# AMP.net
KiCad netlist of a schematic drawn in Altium Designer
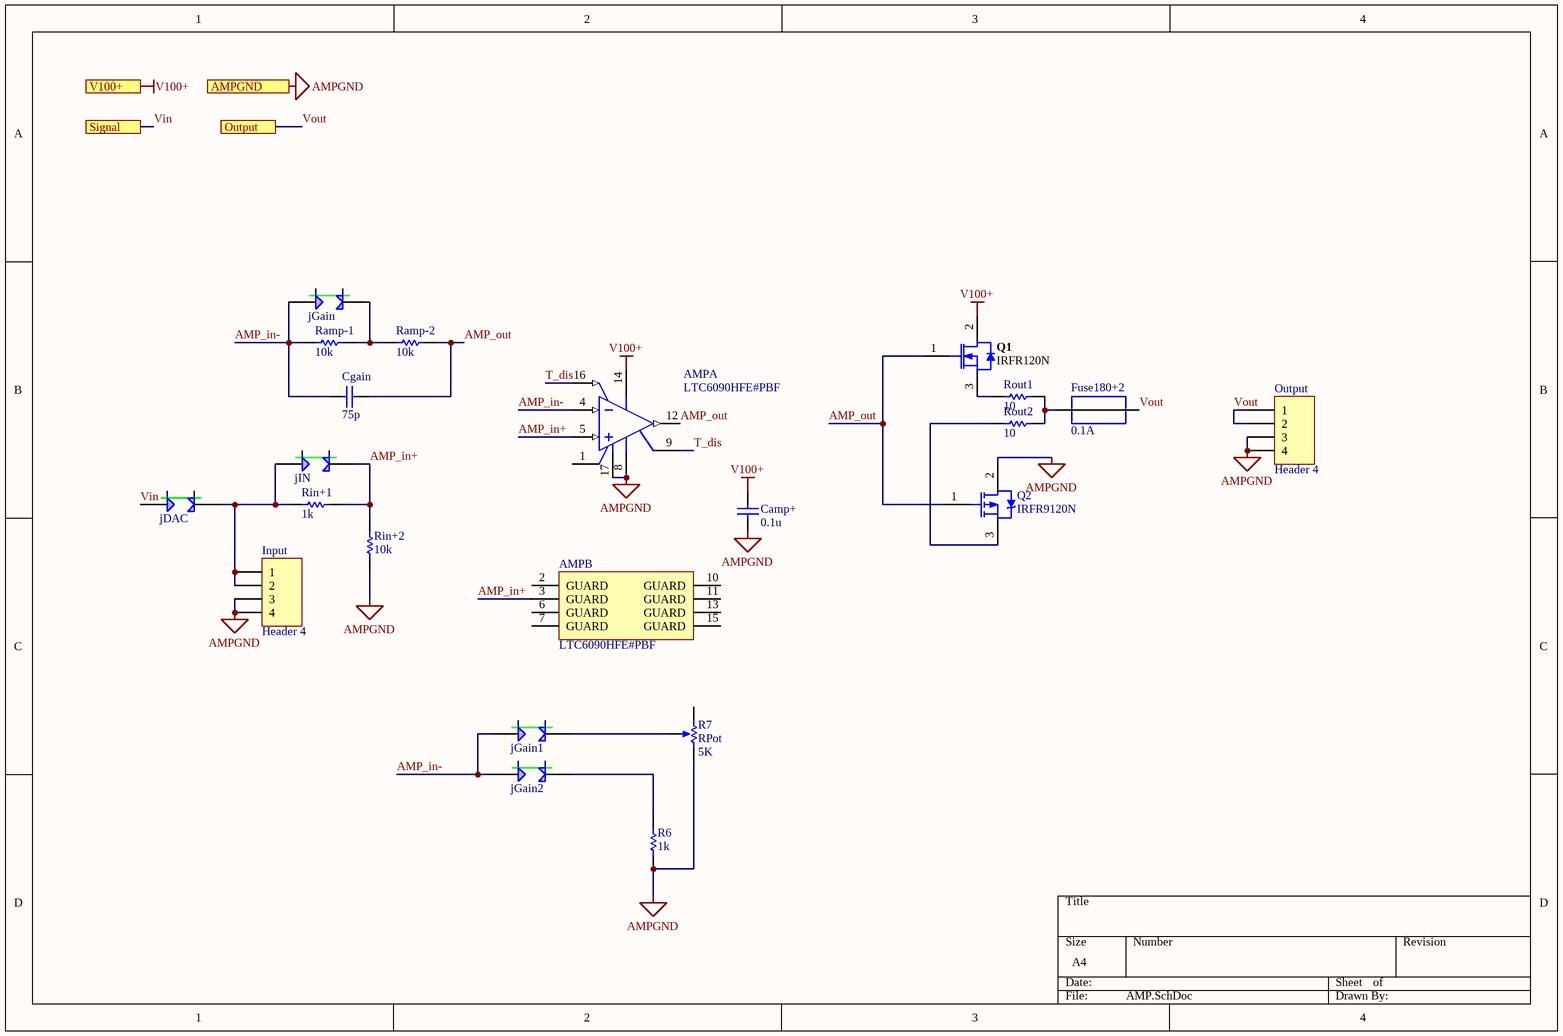
[diagram p0: AMP.SchDoc]

(export (version "E")
  (design (tool "Eeschema 10.0.6"))
  (components
    (comp (ref "AMP")
      (value "LTC6090HFE#PBF")
      (footprint "LT-FE-16-EPV-BA_N")
      (fields
        (field (name "LINEAR TECHNOLOGY PART NUMBER") "LTC6090")
        (field (name "MANUFACTURER") "Linear Technology")
      )
      (libsource (lib "Linear Technology Operational Amplifiers (LT2000-LT6000)") (part "LTC6090HFE#PBF"))
    )
    (comp (ref "Camp+")
      (value "0.1u")
      (footprint "C_0805")
      (description "Capacitor (Semiconductor SIM Model)")
      (fields (field (name "PARTNO") "445-6808-1-ND"))
      (libsource (lib "Lib_AMNL") (part "Csemi"))
    )
    (comp (ref "Cgain")
      (value "75p")
      (footprint "AXIAL-0.5")
      (description "Capacitor (Semiconductor SIM Model)")
      (fields (field (name "PARTNO") "?"))
      (libsource (lib "Lib_AMNL") (part "Cfilm"))
    )
    (comp (ref "Fuse180+2")
      (value "0.1A")
      (footprint "FuseHolder")
      (fields (field (name "PARTNO") "?") (field (name "Comment") "Fuse"))
      (libsource (lib "Lib_AMNL") (part "Fuse"))
    )
    (comp (ref "Input")
      (value "Header 4")
      (footprint "HDR1X4")
      (description "Header, 4-Pin")
      (fields (field (name "PUBLISHER") "Altium Limited"))
      (libsource (lib "Miscellaneous Connectors") (part "Header 4"))
    )
    (comp (ref "jDAC")
      (value "Jumper")
      (footprint "HDR1X2")
      (description "solderable jumper")
      (libsource (lib "Lib_AMNL") (part "Jumper"))
    )
    (comp (ref "jGain")
      (value "Jumper")
      (footprint "HDR1X2")
      (description "solderable jumper")
      (libsource (lib "Lib_AMNL") (part "Jumper"))
    )
    (comp (ref "jGain1")
      (value "Jumper")
      (footprint "HDR1X2")
      (description "solderable jumper")
      (libsource (lib "Lib_AMNL") (part "Jumper"))
    )
    (comp (ref "jGain2")
      (value "Jumper")
      (footprint "HDR1X2")
      (description "solderable jumper")
      (libsource (lib "Lib_AMNL") (part "Jumper"))
    )
    (comp (ref "jIN")
      (value "Jumper")
      (footprint "HDR1X2")
      (description "solderable jumper")
      (libsource (lib "Lib_AMNL") (part "Jumper"))
    )
    (comp (ref "Output")
      (value "Header 4")
      (footprint "HDR1X4")
      (description "Header, 4-Pin")
      (fields (field (name "PUBLISHER") "Altium Limited"))
      (libsource (lib "Miscellaneous Connectors") (part "Header 4"))
    )
    (comp (ref "Q1")
      (value "IRFR120N")
      (footprint "INF-PG-TO252")
      (fields (field (name "MANUFACTURER") "Infineon") (field (name "PARTNUMBER") "2N7002"))
      (libsource (lib "Infineon_Power_MOSFET") (part "IRFR120N"))
    )
    (comp (ref "Q2")
      (value "IRFR9120N")
      (footprint "INF-PG-TO252")
      (fields (field (name "MANUFACTURER") "Infineon") (field (name "PARTNUMBER") "BSL307SP"))
      (libsource (lib "Infineon_Power_MOSFET") (part "IRFR9120N"))
    )
    (comp (ref "R6")
      (value "1k")
      (footprint "0805")
      (description "Semiconductor Resistor, SMD")
      (fields (field (name "PARTNO") "?"))
      (libsource (lib "Lib_AMNL") (part "Rsemi"))
    )
    (comp (ref "R7")
      (value "RPot")
      (footprint "VR5")
      (description "Potentiometer")
      (fields (field (name "ALTIUM_VALUE") "5K") (field (name "PUBLISHER") "Altium Limited"))
      (libsource (lib "Miscellaneous Devices") (part "RPot"))
    )
    (comp (ref "Ramp-1")
      (value "10k")
      (footprint "AXIAL-0.5")
      (description "Semiconductor Resistor, SMD")
      (fields (field (name "PARTNO") "?"))
      (libsource (lib "Lib_AMNL") (part "Rth"))
    )
    (comp (ref "Ramp-2")
      (value "10k")
      (footprint "AXIAL-0.5")
      (description "Semiconductor Resistor, SMD")
      (fields (field (name "PARTNO") "?"))
      (libsource (lib "Lib_AMNL") (part "Rth"))
    )
    (comp (ref "Rin+1")
      (value "1k")
      (footprint "0805")
      (description "Semiconductor Resistor, SMD")
      (fields (field (name "PARTNO") "?"))
      (libsource (lib "Lib_AMNL") (part "Rsemi"))
    )
    (comp (ref "Rin+2")
      (value "10k")
      (footprint "0805")
      (description "Semiconductor Resistor, SMD")
      (fields (field (name "PARTNO") "?"))
      (libsource (lib "Lib_AMNL") (part "Rsemi"))
    )
    (comp (ref "Rout1")
      (value "10")
      (footprint "Res_5w")
      (description "Semiconductor Resistor, SMD")
      (fields (field (name "PARTNO") "?"))
      (libsource (lib "Lib_AMNL") (part "Rsemi"))
    )
    (comp (ref "Rout2")
      (value "10")
      (footprint "Res_5w")
      (description "Semiconductor Resistor, SMD")
      (fields (field (name "PARTNO") "?"))
      (libsource (lib "Lib_AMNL") (part "Rsemi"))
    )
  )
  (nets
    (net (code "1") (name "/AMP_in+") (class "Default")
      (node (ref "AMP") (pin "3") (pinfunction "GUARD_3") (pintype "passive"))
      (node (ref "AMP") (pin "5") (pinfunction "+IN_5") (pintype "input"))
      (node (ref "Rin+1") (pin "2") (pinfunction "2_2") (pintype "passive"))
      (node (ref "Rin+2") (pin "2") (pinfunction "2_2") (pintype "passive"))
      (node (ref "jIN") (pin "2") (pinfunction "2_2") (pintype "passive"))
    )
    (net (code "2") (name "/AMP_in-") (class "Default")
      (node (ref "AMP") (pin "4") (pinfunction "-IN_4") (pintype "input"))
      (node (ref "Cgain") (pin "1") (pinfunction "1_1") (pintype "passive"))
      (node (ref "Ramp-1") (pin "1") (pinfunction "1_1") (pintype "passive"))
      (node (ref "jGain") (pin "1") (pinfunction "1_1") (pintype "passive"))
      (node (ref "jGain1") (pin "1") (pinfunction "1_1") (pintype "passive"))
      (node (ref "jGain2") (pin "1") (pinfunction "1_1") (pintype "passive"))
    )
    (net (code "3") (name "/AMP_out") (class "Default")
      (node (ref "AMP") (pin "12") (pinfunction "OUT_12") (pintype "output"))
      (node (ref "Cgain") (pin "2") (pinfunction "2_2") (pintype "passive"))
      (node (ref "Q1") (pin "1") (pinfunction "GATE_1") (pintype "passive"))
      (node (ref "Q2") (pin "1") (pinfunction "GATE_1") (pintype "passive"))
      (node (ref "Ramp-2") (pin "2") (pinfunction "2_2") (pintype "passive"))
    )
    (net (code "4") (name "/T_dis") (class "Default")
      (node (ref "AMP") (pin "16") (pinfunction "~{OD}_16") (pintype "input"))
      (node (ref "AMP") (pin "9") (pinfunction "~{TFLAG}_9") (pintype "open_collector"))
    )
    (net (code "5") (name "/Vin") (class "Default")
      (node (ref "jDAC") (pin "1") (pinfunction "1_1") (pintype "passive"))
    )
    (net (code "6") (name "/Vout") (class "Default")
      (node (ref "Fuse180+2") (pin "2") (pinfunction "2_2") (pintype "power_in"))
      (node (ref "Output") (pin "1") (pinfunction "1_1") (pintype "passive"))
      (node (ref "Output") (pin "2") (pinfunction "2_2") (pintype "passive"))
    )
    (net (code "7") (name "AMPGND") (class "Default")
      (node (ref "AMP") (pin "17") (pinfunction "EP_17") (pintype "power_in"))
      (node (ref "AMP") (pin "8") (pinfunction "V-_8") (pintype "power_in"))
      (node (ref "Camp+") (pin "1") (pinfunction "1_1") (pintype "passive"))
      (node (ref "Input") (pin "3") (pinfunction "3_3") (pintype "passive"))
      (node (ref "Input") (pin "4") (pinfunction "4_4") (pintype "passive"))
      (node (ref "Output") (pin "3") (pinfunction "3_3") (pintype "passive"))
      (node (ref "Output") (pin "4") (pinfunction "4_4") (pintype "passive"))
      (node (ref "Q2") (pin "2") (pinfunction "DRAIN_2") (pintype "passive"))
      (node (ref "R6") (pin "1") (pinfunction "1_1") (pintype "passive"))
      (node (ref "R7") (pin "2") (pinfunction "BOT_2") (pintype "passive"))
      (node (ref "Rin+2") (pin "1") (pinfunction "1_1") (pintype "passive"))
    )
    (net (code "8") (name "Net-(Fuse180+2-Pad1)") (class "Default")
      (node (ref "Fuse180+2") (pin "1") (pinfunction "1_1") (pintype "power_in"))
      (node (ref "Rout1") (pin "2") (pinfunction "2_2") (pintype "passive"))
      (node (ref "Rout2") (pin "2") (pinfunction "2_2") (pintype "passive"))
    )
    (net (code "9") (name "Net-(Input-Pad1)") (class "Default")
      (node (ref "Input") (pin "1") (pinfunction "1_1") (pintype "passive"))
      (node (ref "Input") (pin "2") (pinfunction "2_2") (pintype "passive"))
      (node (ref "Rin+1") (pin "1") (pinfunction "1_1") (pintype "passive"))
      (node (ref "jDAC") (pin "2") (pinfunction "2_2") (pintype "passive"))
      (node (ref "jIN") (pin "1") (pinfunction "1_1") (pintype "passive"))
    )
    (net (code "10") (name "Net-(Q1-SOURCE)") (class "Default")
      (node (ref "Q1") (pin "3") (pinfunction "SOURCE_3") (pintype "passive"))
      (node (ref "Rout1") (pin "1") (pinfunction "1_1") (pintype "passive"))
    )
    (net (code "11") (name "Net-(Q2-SOURCE)") (class "Default")
      (node (ref "Q2") (pin "3") (pinfunction "SOURCE_3") (pintype "passive"))
      (node (ref "Rout2") (pin "1") (pinfunction "1_1") (pintype "passive"))
    )
    (net (code "12") (name "Net-(R6-Pad2)") (class "Default")
      (node (ref "R6") (pin "2") (pinfunction "2_2") (pintype "passive"))
      (node (ref "jGain2") (pin "2") (pinfunction "2_2") (pintype "passive"))
    )
    (net (code "13") (name "Net-(R7-TAP)") (class "Default")
      (node (ref "R7") (pin "3") (pinfunction "TAP_3") (pintype "passive"))
      (node (ref "jGain1") (pin "2") (pinfunction "2_2") (pintype "passive"))
    )
    (net (code "14") (name "Net-(Ramp-1-Pad2)") (class "Default")
      (node (ref "Ramp-1") (pin "2") (pinfunction "2_2") (pintype "passive"))
      (node (ref "Ramp-2") (pin "1") (pinfunction "1_1") (pintype "passive"))
      (node (ref "jGain") (pin "2") (pinfunction "2_2") (pintype "passive"))
    )
    (net (code "15") (name "V100+") (class "Default")
      (node (ref "AMP") (pin "14") (pinfunction "V+_14") (pintype "power_in"))
      (node (ref "Camp+") (pin "2") (pinfunction "2_2") (pintype "passive"))
      (node (ref "Q1") (pin "2") (pinfunction "DRAIN_2") (pintype "passive"))
    )
    (net (code "16") (name "unconnected-(AMPA-COM-Pad1)") (class "Default")
      (node (ref "AMP") (pin "1") (pinfunction "COM_1") (pintype "passive"))
    )
    (net (code "17") (name "unconnected-(AMPB-GUARD-Pad2)") (class "Default")
      (node (ref "AMP") (pin "2") (pinfunction "GUARD_2") (pintype "passive"))
    )
    (net (code "18") (name "unconnected-(AMPB-GUARD-Pad6)") (class "Default")
      (node (ref "AMP") (pin "6") (pinfunction "GUARD_6") (pintype "passive"))
    )
    (net (code "19") (name "unconnected-(AMPB-GUARD-Pad7)") (class "Default")
      (node (ref "AMP") (pin "7") (pinfunction "GUARD_7") (pintype "passive"))
    )
    (net (code "20") (name "unconnected-(AMPB-GUARD-Pad10)") (class "Default")
      (node (ref "AMP") (pin "10") (pinfunction "GUARD_10") (pintype "passive"))
    )
    (net (code "21") (name "unconnected-(AMPB-GUARD-Pad11)") (class "Default")
      (node (ref "AMP") (pin "11") (pinfunction "GUARD_11") (pintype "passive"))
    )
    (net (code "22") (name "unconnected-(AMPB-GUARD-Pad13)") (class "Default")
      (node (ref "AMP") (pin "13") (pinfunction "GUARD_13") (pintype "passive"))
    )
    (net (code "23") (name "unconnected-(AMPB-GUARD-Pad15)") (class "Default")
      (node (ref "AMP") (pin "15") (pinfunction "GUARD_15") (pintype "passive"))
    )
    (net (code "24") (name "unconnected-(R7-TOP-Pad1)") (class "Default")
      (node (ref "R7") (pin "1") (pinfunction "TOP_1") (pintype "passive"))
    )
  )
)
